# EasyEDA_file.net
KiCad netlist of a schematic drawn in EasyEDA Pro
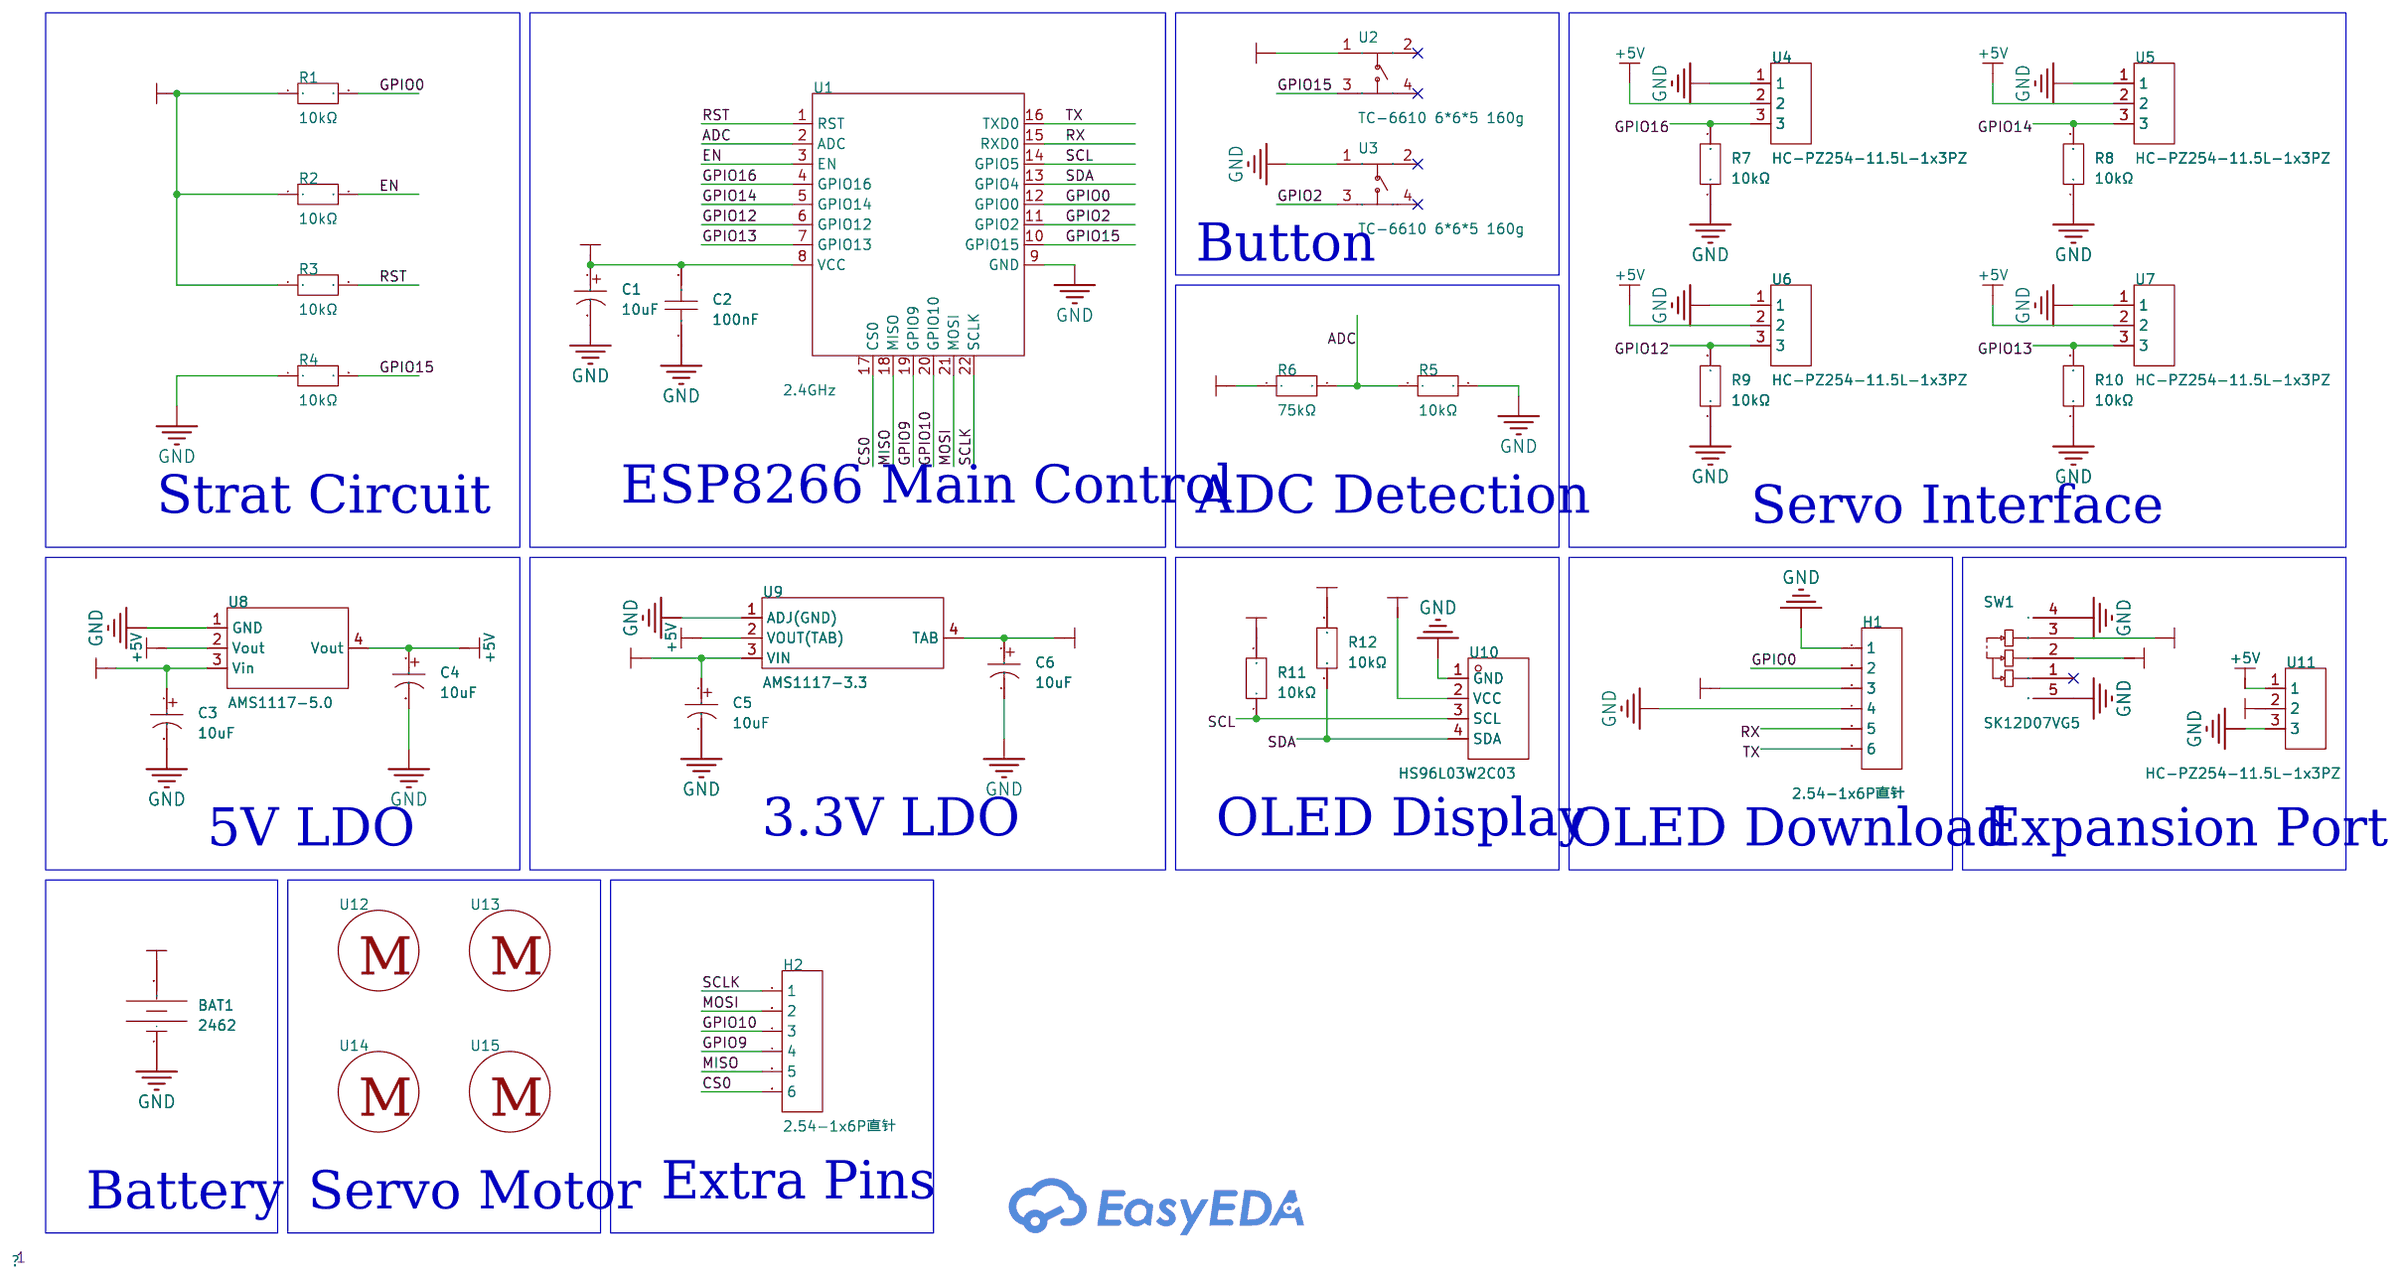
[diagram p0: schematic sheet]

(export (version "E")
  (design (tool "Eeschema 10.0.6"))
  (components
    (comp (ref "BAT1")
      (value "2462")
      (footprint "easyedapro:BAT-TH_2P-P14.50_2462")
      (fields (field (name "Manufacturer") "Keystone"))
      (libsource (lib "easyedapro") (part "2462"))
    )
    (comp (ref "C1")
      (value "10uF")
      (footprint "easyedapro:CAP-TH_BD4.0-P1.50-D0.8-FD")
      (fields
        (field (name "Manufacturer Part") "KS106M025C07RR0VH2FP0")
        (field (name "Manufacturer") "Chengx(承兴)")
      )
      (libsource (lib "easyedapro") (part "10uF 25V 4*7"))
    )
    (comp (ref "C2")
      (value "100nF")
      (footprint "easyedapro:CAP-TH_L4.2-W3.5-P2.54-D0.5")
      (fields (field (name "Manufacturer Part") "178MU0006") (field (name "Manufacturer") "KNSCHA(科尼盛)"))
      (libsource (lib "easyedapro") (part "178MU0006"))
    )
    (comp (ref "C3")
      (value "10uF")
      (footprint "easyedapro:CAP-TH_BD4.0-P1.50-D0.8-FD")
      (fields
        (field (name "Manufacturer Part") "KS106M025C07RR0VH2FP0")
        (field (name "Manufacturer") "Chengx(承兴)")
      )
      (libsource (lib "easyedapro") (part "10uF 25V 4*7"))
    )
    (comp (ref "C4")
      (value "10uF")
      (footprint "easyedapro:CAP-TH_BD4.0-P1.50-D0.8-FD")
      (fields
        (field (name "Manufacturer Part") "KS106M025C07RR0VH2FP0")
        (field (name "Manufacturer") "Chengx(承兴)")
      )
      (libsource (lib "easyedapro") (part "10uF 25V 4*7"))
    )
    (comp (ref "C5")
      (value "10uF")
      (footprint "easyedapro:CAP-TH_BD4.0-P1.50-D0.8-FD")
      (fields
        (field (name "Manufacturer Part") "KS106M025C07RR0VH2FP0")
        (field (name "Manufacturer") "Chengx(承兴)")
      )
      (libsource (lib "easyedapro") (part "10uF 25V 4*7"))
    )
    (comp (ref "C6")
      (value "10uF")
      (footprint "easyedapro:CAP-TH_BD4.0-P1.50-D0.8-FD")
      (fields
        (field (name "Manufacturer Part") "KS106M025C07RR0VH2FP0")
        (field (name "Manufacturer") "Chengx(承兴)")
      )
      (libsource (lib "easyedapro") (part "10uF 25V 4*7"))
    )
    (comp (ref "H1")
      (value "2.54-1x6P直针")
      (footprint "easyedapro:HDR-TH_6P-P2.54-V-M-1")
      (fields (field (name "Manufacturer") "BOOMELE(博穆精密)"))
      (libsource (lib "easyedapro") (part "Header-Male-2.54_1x6"))
    )
    (comp (ref "H2")
      (value "2.54-1x6P直针")
      (footprint "easyedapro:HDR-TH_6P-P2.54-V-M-1")
      (fields (field (name "Manufacturer") "BOOMELE(博穆精密)"))
      (libsource (lib "easyedapro") (part "Header-Male-2.54_1x6"))
    )
    (comp (ref "R1")
      (value "10kΩ")
      (footprint "easyedapro:RES-TH_BD2.4-L6.3-P10.30-D0.6")
      (fields
        (field (name "Manufacturer Part") "RN1/4W10KFT/BA1")
        (field (name "Manufacturer") "Tyohm(幸亚电阻)")
      )
      (libsource (lib "easyedapro") (part "RN 1/4W 10K F T/B A1"))
    )
    (comp (ref "R2")
      (value "10kΩ")
      (footprint "easyedapro:RES-TH_BD2.4-L6.3-P10.30-D0.6")
      (fields
        (field (name "Manufacturer Part") "RN1/4W10KFT/BA1")
        (field (name "Manufacturer") "Tyohm(幸亚电阻)")
      )
      (libsource (lib "easyedapro") (part "RN 1/4W 10K F T/B A1"))
    )
    (comp (ref "R3")
      (value "10kΩ")
      (footprint "easyedapro:RES-TH_BD2.4-L6.3-P10.30-D0.6")
      (fields
        (field (name "Manufacturer Part") "RN1/4W10KFT/BA1")
        (field (name "Manufacturer") "Tyohm(幸亚电阻)")
      )
      (libsource (lib "easyedapro") (part "RN 1/4W 10K F T/B A1"))
    )
    (comp (ref "R4")
      (value "10kΩ")
      (footprint "easyedapro:RES-TH_BD2.4-L6.3-P10.30-D0.6")
      (fields
        (field (name "Manufacturer Part") "RN1/4W10KFT/BA1")
        (field (name "Manufacturer") "Tyohm(幸亚电阻)")
      )
      (libsource (lib "easyedapro") (part "RN 1/4W 10K F T/B A1"))
    )
    (comp (ref "R5")
      (value "10kΩ")
      (footprint "easyedapro:RES-TH_BD2.4-L6.3-P10.30-D0.6")
      (fields
        (field (name "Manufacturer Part") "RN1/4W10KFT/BA1")
        (field (name "Manufacturer") "Tyohm(幸亚电阻)")
      )
      (libsource (lib "easyedapro") (part "RN 1/4W 10K F T/B A1"))
    )
    (comp (ref "R6")
      (value "75kΩ")
      (footprint "easyedapro:RES-TH_BD2.4-L6.3-P10.30-D0.6")
      (fields
        (field (name "Manufacturer Part") "RN 1/4W 75K F T/B A1")
        (field (name "Manufacturer") "Tyohm(幸亚电阻)")
      )
      (libsource (lib "easyedapro") (part "RN 1/4W 75K F T/B A1"))
    )
    (comp (ref "R7")
      (value "10kΩ")
      (footprint "easyedapro:RES-TH_BD2.4-L6.3-P10.30-D0.6")
      (fields
        (field (name "Manufacturer Part") "RN1/4W10KFT/BA1")
        (field (name "Manufacturer") "Tyohm(幸亚电阻)")
      )
      (libsource (lib "easyedapro") (part "RN 1/4W 10K F T/B A1"))
    )
    (comp (ref "R8")
      (value "10kΩ")
      (footprint "easyedapro:RES-TH_BD2.4-L6.3-P10.30-D0.6")
      (fields
        (field (name "Manufacturer Part") "RN1/4W10KFT/BA1")
        (field (name "Manufacturer") "Tyohm(幸亚电阻)")
      )
      (libsource (lib "easyedapro") (part "RN 1/4W 10K F T/B A1"))
    )
    (comp (ref "R9")
      (value "10kΩ")
      (footprint "easyedapro:RES-TH_BD2.4-L6.3-P10.30-D0.6")
      (fields
        (field (name "Manufacturer Part") "RN1/4W10KFT/BA1")
        (field (name "Manufacturer") "Tyohm(幸亚电阻)")
      )
      (libsource (lib "easyedapro") (part "RN 1/4W 10K F T/B A1"))
    )
    (comp (ref "R10")
      (value "10kΩ")
      (footprint "easyedapro:RES-TH_BD2.4-L6.3-P10.30-D0.6")
      (fields
        (field (name "Manufacturer Part") "RN1/4W10KFT/BA1")
        (field (name "Manufacturer") "Tyohm(幸亚电阻)")
      )
      (libsource (lib "easyedapro") (part "RN 1/4W 10K F T/B A1"))
    )
    (comp (ref "R11")
      (value "10kΩ")
      (footprint "easyedapro:RES-TH_BD2.4-L6.3-P10.30-D0.6")
      (fields
        (field (name "Manufacturer Part") "RN1/4W10KFT/BA1")
        (field (name "Manufacturer") "Tyohm(幸亚电阻)")
      )
      (libsource (lib "easyedapro") (part "RN 1/4W 10K F T/B A1"))
    )
    (comp (ref "R12")
      (value "10kΩ")
      (footprint "easyedapro:RES-TH_BD2.4-L6.3-P10.30-D0.6")
      (fields
        (field (name "Manufacturer Part") "RN1/4W10KFT/BA1")
        (field (name "Manufacturer") "Tyohm(幸亚电阻)")
      )
      (libsource (lib "easyedapro") (part "RN 1/4W 10K F T/B A1"))
    )
    (comp (ref "SW1")
      (value "SK12D07VG5")
      (footprint "easyedapro:SW-TH_SK12D07VG5-1")
      (fields (field (name "Manufacturer") "SHOU HAN(首韩)"))
      (libsource (lib "easyedapro") (part "SK12D07VG5"))
    )
    (comp (ref "U1")
      (value "2.4GHz")
      (footprint "easyedapro:WIFIM-SMD_ESP-12F-ESP8266MOD")
      (fields
        (field (name "Manufacturer Part") "ESP-12F(ESP8266MOD)")
        (field (name "Manufacturer") "Ai-Thinker(安信可)")
      )
      (libsource (lib "easyedapro") (part "ESP-12F(ESP8266MOD)"))
    )
    (comp (ref "U2")
      (value "TC-6610 6*6*5 160g")
      (footprint "easyedapro:SW-TH_4P-L6.0-W6.0-P4.50-LS6.5")
      (fields (field (name "Manufacturer") "FG(富港)"))
      (libsource (lib "easyedapro") (part "TC-6610 6*6*5 160G"))
    )
    (comp (ref "U3")
      (value "TC-6610 6*6*5 160g")
      (footprint "easyedapro:SW-TH_4P-L6.0-W6.0-P4.50-LS6.5")
      (fields (field (name "Manufacturer") "FG(富港)"))
      (libsource (lib "easyedapro") (part "TC-6610 6*6*5 160G"))
    )
    (comp (ref "U4")
      (value "HC-PZ254-11.5L-1x3PZ")
      (footprint "easyedapro:HDR-TH_3P-P2.54-V-M")
      (fields (field (name "Manufacturer") "HC(虹成电子)"))
      (libsource (lib "easyedapro") (part "HC-PZ254-11.5L-1X3PZ"))
    )
    (comp (ref "U5")
      (value "HC-PZ254-11.5L-1x3PZ")
      (footprint "easyedapro:HDR-TH_3P-P2.54-V-M")
      (fields (field (name "Manufacturer") "HC(虹成电子)"))
      (libsource (lib "easyedapro") (part "HC-PZ254-11.5L-1X3PZ"))
    )
    (comp (ref "U6")
      (value "HC-PZ254-11.5L-1x3PZ")
      (footprint "easyedapro:HDR-TH_3P-P2.54-V-M")
      (fields (field (name "Manufacturer") "HC(虹成电子)"))
      (libsource (lib "easyedapro") (part "HC-PZ254-11.5L-1X3PZ"))
    )
    (comp (ref "U7")
      (value "HC-PZ254-11.5L-1x3PZ")
      (footprint "easyedapro:HDR-TH_3P-P2.54-V-M")
      (fields (field (name "Manufacturer") "HC(虹成电子)"))
      (libsource (lib "easyedapro") (part "HC-PZ254-11.5L-1X3PZ"))
    )
    (comp (ref "U8")
      (value "AMS1117-5.0")
      (footprint "easyedapro:SOT-223-4_L6.5-W3.5-P2.30-LS7.0-BR")
      (fields (field (name "Manufacturer") "HXY MOSFET(华轩阳电子)"))
      (libsource (lib "easyedapro") (part "AMS1117-5.0_C5345984"))
    )
    (comp (ref "U9")
      (value "AMS1117-3.3")
      (footprint "easyedapro:SOT-223-4_L6.5-W3.5-P2.30-LS7.0-BR")
      (fields (field (name "Manufacturer") "UMW(友台半导体)"))
      (libsource (lib "easyedapro") (part "AMS1117-3.3_C347222"))
    )
    (comp (ref "U10")
      (value "HS96L03W2C03")
      (footprint "easyedapro:OLED-TH_L27.8-W27.2-P2.54_C9900033791")
      (fields (field (name "Manufacturer") "HS(汉昇)"))
      (libsource (lib "easyedapro") (part "HS96L03W2C03"))
    )
    (comp (ref "U11")
      (value "HC-PZ254-11.5L-1x3PZ")
      (footprint "easyedapro:HDR-TH_3P-P2.54-V-M")
      (fields (field (name "Manufacturer") "HC(虹成电子)"))
      (libsource (lib "easyedapro") (part "HC-PZ254-11.5L-1X3PZ"))
    )
    (comp (ref "U12")
      (value "~")
      (footprint "easyedapro:Servo")
      (libsource (lib "easyedapro") (part "Servo"))
    )
    (comp (ref "U13")
      (value "~")
      (footprint "easyedapro:Servo")
      (libsource (lib "easyedapro") (part "Servo"))
    )
    (comp (ref "U14")
      (value "~")
      (footprint "easyedapro:Servo")
      (libsource (lib "easyedapro") (part "Servo"))
    )
    (comp (ref "U15")
      (value "~")
      (footprint "easyedapro:Servo")
      (libsource (lib "easyedapro") (part "Servo"))
    )
  )
  (nets
    (net (code "1") (name "+3.3V") (class "Default")
      (node (ref "C1") (pin "1") (pinfunction "1_1") (pintype "input"))
      (node (ref "C2") (pin "2") (pinfunction "2_2") (pintype "unspecified"))
      (node (ref "C6") (pin "1") (pinfunction "1_1") (pintype "input"))
      (node (ref "H1") (pin "3") (pinfunction "3_3") (pintype "input"))
      (node (ref "R1") (pin "1") (pinfunction "1_1") (pintype "unspecified"))
      (node (ref "R11") (pin "2") (pinfunction "2_2") (pintype "unspecified"))
      (node (ref "R12") (pin "2") (pinfunction "2_2") (pintype "unspecified"))
      (node (ref "R2") (pin "1") (pinfunction "1_1") (pintype "unspecified"))
      (node (ref "R3") (pin "1") (pinfunction "1_1") (pintype "unspecified"))
      (node (ref "U1") (pin "8") (pinfunction "VCC_8") (pintype "unspecified"))
      (node (ref "U10") (pin "2") (pinfunction "VCC_2") (pintype "unspecified"))
      (node (ref "U2") (pin "1") (pinfunction "1_1") (pintype "unspecified"))
      (node (ref "U9") (pin "4") (pinfunction "TAB_4") (pintype "unspecified"))
    )
    (net (code "2") (name "+5V") (class "Default")
      (node (ref "C4") (pin "1") (pinfunction "1_1") (pintype "input"))
      (node (ref "U11") (pin "1") (pinfunction "1_1") (pintype "unspecified"))
      (node (ref "U4") (pin "2") (pinfunction "2_2") (pintype "unspecified"))
      (node (ref "U5") (pin "2") (pinfunction "2_2") (pintype "unspecified"))
      (node (ref "U6") (pin "2") (pinfunction "2_2") (pintype "unspecified"))
      (node (ref "U7") (pin "2") (pinfunction "2_2") (pintype "unspecified"))
      (node (ref "U8") (pin "2") (pinfunction "Vout_2") (pintype "unspecified"))
      (node (ref "U8") (pin "4") (pinfunction "Vout_4") (pintype "unspecified"))
      (node (ref "U9") (pin "2") (pinfunction "VOUT(TAB)_2") (pintype "unspecified"))
    )
    (net (code "3") (name "/ADC") (class "Default")
      (node (ref "R5") (pin "1") (pinfunction "1_1") (pintype "unspecified"))
      (node (ref "R6") (pin "2") (pinfunction "2_2") (pintype "unspecified"))
      (node (ref "U1") (pin "2") (pinfunction "ADC_2") (pintype "unspecified"))
    )
    (net (code "4") (name "/CS0") (class "Default")
      (node (ref "H2") (pin "6") (pinfunction "6_6") (pintype "input"))
      (node (ref "U1") (pin "17") (pinfunction "CS0_17") (pintype "unspecified"))
    )
    (net (code "5") (name "/EN") (class "Default")
      (node (ref "R2") (pin "2") (pinfunction "2_2") (pintype "unspecified"))
      (node (ref "U1") (pin "3") (pinfunction "EN_3") (pintype "unspecified"))
    )
    (net (code "6") (name "/GPIO0") (class "Default")
      (node (ref "H1") (pin "2") (pinfunction "2_2") (pintype "input"))
      (node (ref "R1") (pin "2") (pinfunction "2_2") (pintype "unspecified"))
      (node (ref "U1") (pin "12") (pinfunction "GPIO0_12") (pintype "unspecified"))
    )
    (net (code "7") (name "/GPIO2") (class "Default")
      (node (ref "U1") (pin "11") (pinfunction "GPIO2_11") (pintype "unspecified"))
      (node (ref "U3") (pin "3") (pinfunction "3_3") (pintype "unspecified"))
    )
    (net (code "8") (name "/GPIO9") (class "Default")
      (node (ref "H2") (pin "4") (pinfunction "4_4") (pintype "input"))
      (node (ref "U1") (pin "19") (pinfunction "GPIO9_19") (pintype "unspecified"))
    )
    (net (code "9") (name "/GPIO10") (class "Default")
      (node (ref "H2") (pin "3") (pinfunction "3_3") (pintype "input"))
      (node (ref "U1") (pin "20") (pinfunction "GPIO10_20") (pintype "unspecified"))
    )
    (net (code "10") (name "/GPIO12") (class "Default")
      (node (ref "R9") (pin "2") (pinfunction "2_2") (pintype "unspecified"))
      (node (ref "U1") (pin "6") (pinfunction "GPIO12_6") (pintype "unspecified"))
      (node (ref "U6") (pin "3") (pinfunction "3_3") (pintype "unspecified"))
    )
    (net (code "11") (name "/GPIO13") (class "Default")
      (node (ref "R10") (pin "2") (pinfunction "2_2") (pintype "unspecified"))
      (node (ref "U1") (pin "7") (pinfunction "GPIO13_7") (pintype "unspecified"))
      (node (ref "U7") (pin "3") (pinfunction "3_3") (pintype "unspecified"))
    )
    (net (code "12") (name "/GPIO14") (class "Default")
      (node (ref "R8") (pin "2") (pinfunction "2_2") (pintype "unspecified"))
      (node (ref "U1") (pin "5") (pinfunction "GPIO14_5") (pintype "unspecified"))
      (node (ref "U5") (pin "3") (pinfunction "3_3") (pintype "unspecified"))
    )
    (net (code "13") (name "/GPIO15") (class "Default")
      (node (ref "R4") (pin "2") (pinfunction "2_2") (pintype "unspecified"))
      (node (ref "U1") (pin "10") (pinfunction "GPIO15_10") (pintype "unspecified"))
      (node (ref "U2") (pin "3") (pinfunction "3_3") (pintype "unspecified"))
    )
    (net (code "14") (name "/GPIO16") (class "Default")
      (node (ref "R7") (pin "2") (pinfunction "2_2") (pintype "unspecified"))
      (node (ref "U1") (pin "4") (pinfunction "GPIO16_4") (pintype "unspecified"))
      (node (ref "U4") (pin "3") (pinfunction "3_3") (pintype "unspecified"))
    )
    (net (code "15") (name "/MISO") (class "Default")
      (node (ref "H2") (pin "5") (pinfunction "5_5") (pintype "input"))
      (node (ref "U1") (pin "18") (pinfunction "MISO_18") (pintype "unspecified"))
    )
    (net (code "16") (name "/MOSI") (class "Default")
      (node (ref "H2") (pin "2") (pinfunction "2_2") (pintype "input"))
      (node (ref "U1") (pin "21") (pinfunction "MOSI_21") (pintype "unspecified"))
    )
    (net (code "17") (name "/RST") (class "Default")
      (node (ref "R3") (pin "2") (pinfunction "2_2") (pintype "unspecified"))
      (node (ref "U1") (pin "1") (pinfunction "RST_1") (pintype "unspecified"))
    )
    (net (code "18") (name "/RX") (class "Default")
      (node (ref "H1") (pin "5") (pinfunction "5_5") (pintype "input"))
      (node (ref "U1") (pin "15") (pinfunction "RXD0_15") (pintype "unspecified"))
    )
    (net (code "19") (name "/SCL") (class "Default")
      (node (ref "R11") (pin "1") (pinfunction "1_1") (pintype "unspecified"))
      (node (ref "U1") (pin "14") (pinfunction "GPIO5_14") (pintype "unspecified"))
      (node (ref "U10") (pin "3") (pinfunction "SCL_3") (pintype "unspecified"))
    )
    (net (code "20") (name "/SCLK") (class "Default")
      (node (ref "H2") (pin "1") (pinfunction "1_1") (pintype "input"))
      (node (ref "U1") (pin "22") (pinfunction "SCLK_22") (pintype "unspecified"))
    )
    (net (code "21") (name "/SDA") (class "Default")
      (node (ref "R12") (pin "1") (pinfunction "1_1") (pintype "unspecified"))
      (node (ref "U1") (pin "13") (pinfunction "GPIO4_13") (pintype "unspecified"))
      (node (ref "U10") (pin "4") (pinfunction "SDA_4") (pintype "unspecified"))
    )
    (net (code "22") (name "/TX") (class "Default")
      (node (ref "H1") (pin "6") (pinfunction "6_6") (pintype "input"))
      (node (ref "U1") (pin "16") (pinfunction "TXD0_16") (pintype "unspecified"))
    )
    (net (code "23") (name "GND") (class "Default")
      (node (ref "BAT1") (pin "1") (pinfunction "-_1") (pintype "unspecified"))
      (node (ref "C1") (pin "2") (pinfunction "2_2") (pintype "input"))
      (node (ref "C2") (pin "1") (pinfunction "1_1") (pintype "unspecified"))
      (node (ref "C3") (pin "2") (pinfunction "2_2") (pintype "input"))
      (node (ref "C4") (pin "2") (pinfunction "2_2") (pintype "input"))
      (node (ref "C5") (pin "2") (pinfunction "2_2") (pintype "input"))
      (node (ref "C6") (pin "2") (pinfunction "2_2") (pintype "input"))
      (node (ref "H1") (pin "1") (pinfunction "1_1") (pintype "input"))
      (node (ref "H1") (pin "4") (pinfunction "4_4") (pintype "input"))
      (node (ref "R10") (pin "1") (pinfunction "1_1") (pintype "unspecified"))
      (node (ref "R4") (pin "1") (pinfunction "1_1") (pintype "unspecified"))
      (node (ref "R5") (pin "2") (pinfunction "2_2") (pintype "unspecified"))
      (node (ref "R7") (pin "1") (pinfunction "1_1") (pintype "unspecified"))
      (node (ref "R8") (pin "1") (pinfunction "1_1") (pintype "unspecified"))
      (node (ref "R9") (pin "1") (pinfunction "1_1") (pintype "unspecified"))
      (node (ref "SW1") (pin "4") (pinfunction "4_4") (pintype "unspecified"))
      (node (ref "SW1") (pin "5") (pinfunction "5_5") (pintype "unspecified"))
      (node (ref "U1") (pin "9") (pinfunction "GND_9") (pintype "unspecified"))
      (node (ref "U10") (pin "1") (pinfunction "GND_1") (pintype "unspecified"))
      (node (ref "U11") (pin "3") (pinfunction "3_3") (pintype "unspecified"))
      (node (ref "U3") (pin "1") (pinfunction "1_1") (pintype "unspecified"))
      (node (ref "U4") (pin "1") (pinfunction "1_1") (pintype "unspecified"))
      (node (ref "U5") (pin "1") (pinfunction "1_1") (pintype "unspecified"))
      (node (ref "U6") (pin "1") (pinfunction "1_1") (pintype "unspecified"))
      (node (ref "U7") (pin "1") (pinfunction "1_1") (pintype "unspecified"))
      (node (ref "U8") (pin "1") (pinfunction "GND_1") (pintype "unspecified"))
      (node (ref "U9") (pin "1") (pinfunction "ADJ(GND)_1") (pintype "unspecified"))
    )
    (net (code "24") (name "VBAT") (class "Default")
      (node (ref "C3") (pin "1") (pinfunction "1_1") (pintype "input"))
      (node (ref "C5") (pin "1") (pinfunction "1_1") (pintype "input"))
      (node (ref "R6") (pin "1") (pinfunction "1_1") (pintype "unspecified"))
      (node (ref "SW1") (pin "3") (pinfunction "3_3") (pintype "unspecified"))
      (node (ref "U8") (pin "3") (pinfunction "Vin_3") (pintype "unspecified"))
      (node (ref "U9") (pin "3") (pinfunction "VIN_3") (pintype "unspecified"))
    )
    (net (code "25") (name "VIN") (class "Default")
      (node (ref "BAT1") (pin "2") (pinfunction "+_2") (pintype "unspecified"))
      (node (ref "SW1") (pin "2") (pinfunction "2_2") (pintype "unspecified"))
      (node (ref "U11") (pin "2") (pinfunction "2_2") (pintype "unspecified"))
    )
    (net (code "26") (name "unconnected-(SW1-Pad1)") (class "Default")
      (node (ref "SW1") (pin "1") (pinfunction "1_1") (pintype "unspecified+no_connect"))
    )
    (net (code "27") (name "unconnected-(U2-Pad2)") (class "Default")
      (node (ref "U2") (pin "2") (pinfunction "2_2") (pintype "unspecified+no_connect"))
    )
    (net (code "28") (name "unconnected-(U2-Pad4)") (class "Default")
      (node (ref "U2") (pin "4") (pinfunction "4_4") (pintype "unspecified+no_connect"))
    )
    (net (code "29") (name "unconnected-(U3-Pad2)") (class "Default")
      (node (ref "U3") (pin "2") (pinfunction "2_2") (pintype "unspecified+no_connect"))
    )
    (net (code "30") (name "unconnected-(U3-Pad4)") (class "Default")
      (node (ref "U3") (pin "4") (pinfunction "4_4") (pintype "unspecified+no_connect"))
    )
  )
)
